# FPGA_IO_Interface.net
KiCad netlist of a schematic drawn in Altium Designer
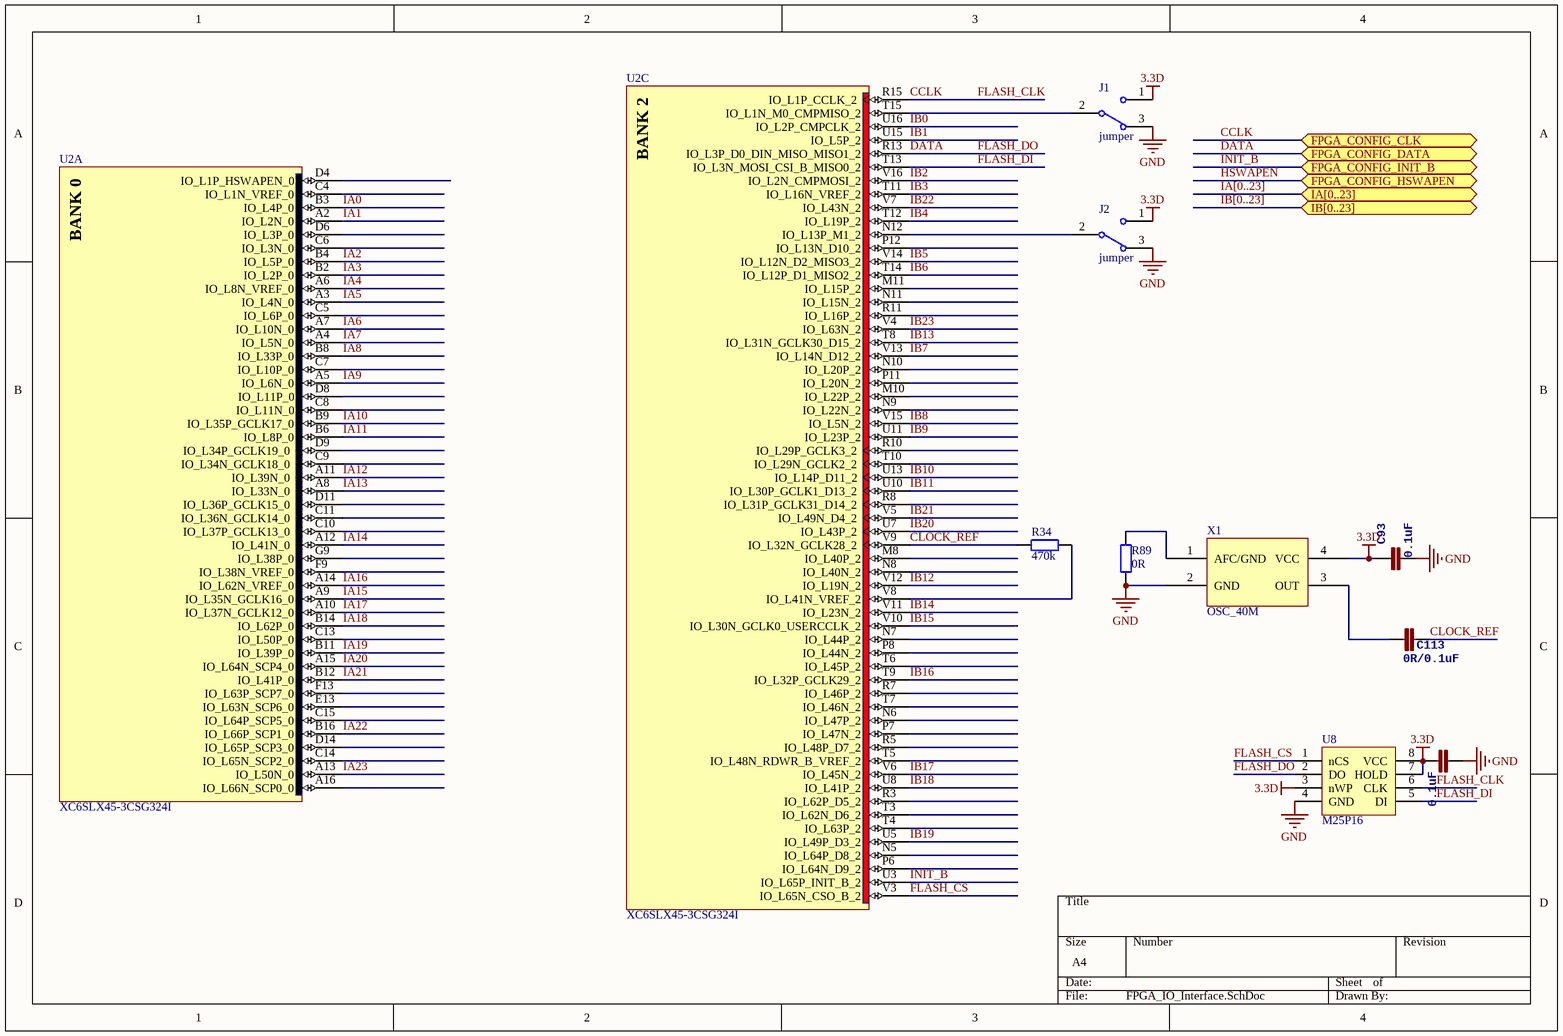
[diagram p0: FPGA_IO_Interface.SchDoc]

(export (version "E")
  (design (tool "Eeschema 10.0.6"))
  (components
    (comp (ref "C68")
      (value "0.1uF")
      (footprint "0402")
      (description "<b>Capacitor</b>\nStandard 0603 ceramic capacitor, and 0.1\" leaded capacitor.")
      (fields (field (name "PARTNO") "CC0402ZRY5V7BB104"))
      (libsource (lib "") (part "CAP0402-CAP_1"))
    )
    (comp (ref "C93")
      (value "0.1uF")
      (footprint "0402")
      (description "<b>Capacitor</b>\nStandard 0603 ceramic capacitor, and 0.1\" leaded capacitor.")
      (fields (field (name "PARTNO") "CC0402ZRY5V7BB104"))
      (libsource (lib "pixhawk2") (part "CAP0402-CAP"))
    )
    (comp (ref "C113")
      (value "0R/0.1uF")
      (footprint "0402")
      (description "<b>Capacitor</b>\nStandard 0603 ceramic capacitor, and 0.1\" leaded capacitor.")
      (fields (field (name "PARTNO") "CC0402ZRY5V7BB104"))
      (libsource (lib "pixhawk2") (part "CAP0402-CAP"))
    )
    (comp (ref "J1")
      (value "jumper")
      (footprint "0402J")
      (description "SPDT Subminiature Toggle Switch, Right Angle Mounting, Vertical Actuation")
      (fields (field (name "PUBLISHER") "Altium Limited"))
      (libsource (lib "Miscellaneous Devices") (part "SW-SPDT"))
    )
    (comp (ref "J2")
      (value "jumper")
      (footprint "0402J")
      (description "SPDT Subminiature Toggle Switch, Right Angle Mounting, Vertical Actuation")
      (fields (field (name "PUBLISHER") "Altium Limited"))
      (libsource (lib "Miscellaneous Devices") (part "SW-SPDT"))
    )
    (comp (ref "R34")
      (value "470k")
      (footprint "0402")
      (description "Resistor")
      (fields (field (name "PUBLISHER") "Altium Limited"))
      (libsource (lib "") (part "Res2_1"))
    )
    (comp (ref "R89")
      (value "0R")
      (footprint "0402")
      (description "Resistor")
      (fields (field (name "PUBLISHER") "Altium Limited"))
      (libsource (lib "Miscellaneous Devices") (part "Res2"))
    )
    (comp (ref "U2")
      (value "XC6SLX45-3CSG324I")
      (footprint "CSG324")
      (fields (field (name "PUBLISHER") "Altium Limited"))
      (libsource (lib "Xilinx Spartan-6") (part "XC6SLX45-3CSG324I"))
    )
    (comp (ref "U8") (value "M25P16") (footprint "SO8") (libsource (lib "sch") (part "M25P16")))
    (comp (ref "X1") (value "OSC_40M") (footprint "TXC_7Q") (libsource (lib "F4SDR") (part "OSC_40M")))
  )
  (nets
    (net (code "1") (name "/CCLK") (class "Default")
      (node (ref "U2") (pin "R15") (pinfunction "IO_L1P_CCLK_2_R15") (pintype "bidirectional"))
      (node (ref "U8") (pin "6") (pinfunction "CLK_6") (pintype "passive"))
    )
    (net (code "2") (name "/CLOCK_REF") (class "Default")
      (node (ref "C113") (pin "2") (pinfunction "2_2") (pintype "passive"))
      (node (ref "R34") (pin "1") (pinfunction "1_1") (pintype "passive"))
      (node (ref "U2") (pin "V9") (pinfunction "IO_L32N_GCLK28_2_V9") (pintype "bidirectional"))
    )
    (net (code "3") (name "/DATA") (class "Default")
      (node (ref "U2") (pin "R13") (pinfunction "IO_L3P_D0_DIN_MISO_MISO1_2_R13") (pintype "bidirectional"))
      (node (ref "U8") (pin "2") (pinfunction "DO_2") (pintype "passive"))
    )
    (net (code "4") (name "/FLASH_CS") (class "Default")
      (node (ref "U2") (pin "V3") (pinfunction "IO_L65N_CSO_B_2_V3") (pintype "bidirectional"))
      (node (ref "U8") (pin "1") (pinfunction "nCS_1") (pintype "passive"))
    )
    (net (code "5") (name "/FLASH_DI") (class "Default")
      (node (ref "U2") (pin "T13") (pinfunction "IO_L3N_MOSI_CSI_B_MISO0_2_T13") (pintype "bidirectional"))
      (node (ref "U8") (pin "5") (pinfunction "DI_5") (pintype "passive"))
    )
    (net (code "7") (name "/IA0") (class "Default")
      (node (ref "U2") (pin "B3") (pinfunction "IO_L4P_0_B3") (pintype "bidirectional"))
    )
    (net (code "8") (name "/IA1") (class "Default")
      (node (ref "U2") (pin "A2") (pinfunction "IO_L2N_0_A2") (pintype "bidirectional"))
    )
    (net (code "9") (name "/IA2") (class "Default")
      (node (ref "U2") (pin "B4") (pinfunction "IO_L5P_0_B4") (pintype "bidirectional"))
    )
    (net (code "10") (name "/IA3") (class "Default")
      (node (ref "U2") (pin "B2") (pinfunction "IO_L2P_0_B2") (pintype "bidirectional"))
    )
    (net (code "11") (name "/IA4") (class "Default")
      (node (ref "U2") (pin "A6") (pinfunction "IO_L8N_VREF_0_A6") (pintype "bidirectional"))
    )
    (net (code "12") (name "/IA5") (class "Default")
      (node (ref "U2") (pin "A3") (pinfunction "IO_L4N_0_A3") (pintype "bidirectional"))
    )
    (net (code "13") (name "/IA6") (class "Default")
      (node (ref "U2") (pin "A7") (pinfunction "IO_L10N_0_A7") (pintype "bidirectional"))
    )
    (net (code "14") (name "/IA7") (class "Default")
      (node (ref "U2") (pin "A4") (pinfunction "IO_L5N_0_A4") (pintype "bidirectional"))
    )
    (net (code "15") (name "/IA8") (class "Default")
      (node (ref "U2") (pin "B8") (pinfunction "IO_L33P_0_B8") (pintype "bidirectional"))
    )
    (net (code "16") (name "/IA9") (class "Default")
      (node (ref "U2") (pin "A5") (pinfunction "IO_L6N_0_A5") (pintype "bidirectional"))
    )
    (net (code "17") (name "/IA10") (class "Default")
      (node (ref "U2") (pin "B9") (pinfunction "IO_L35P_GCLK17_0_B9") (pintype "bidirectional"))
    )
    (net (code "18") (name "/IA11") (class "Default")
      (node (ref "U2") (pin "B6") (pinfunction "IO_L8P_0_B6") (pintype "bidirectional"))
    )
    (net (code "19") (name "/IA12") (class "Default")
      (node (ref "U2") (pin "A11") (pinfunction "IO_L39N_0_A11") (pintype "bidirectional"))
    )
    (net (code "20") (name "/IA13") (class "Default")
      (node (ref "U2") (pin "A8") (pinfunction "IO_L33N_0_A8") (pintype "bidirectional"))
    )
    (net (code "21") (name "/IA14") (class "Default")
      (node (ref "U2") (pin "A12") (pinfunction "IO_L41N_0_A12") (pintype "bidirectional"))
    )
    (net (code "22") (name "/IA15") (class "Default")
      (node (ref "U2") (pin "A9") (pinfunction "IO_L35N_GCLK16_0_A9") (pintype "bidirectional"))
    )
    (net (code "23") (name "/IA16") (class "Default")
      (node (ref "U2") (pin "A14") (pinfunction "IO_L62N_VREF_0_A14") (pintype "bidirectional"))
    )
    (net (code "24") (name "/IA17") (class "Default")
      (node (ref "U2") (pin "A10") (pinfunction "IO_L37N_GCLK12_0_A10") (pintype "bidirectional"))
    )
    (net (code "25") (name "/IA18") (class "Default")
      (node (ref "U2") (pin "B14") (pinfunction "IO_L62P_0_B14") (pintype "bidirectional"))
    )
    (net (code "26") (name "/IA19") (class "Default")
      (node (ref "U2") (pin "B11") (pinfunction "IO_L39P_0_B11") (pintype "bidirectional"))
    )
    (net (code "27") (name "/IA20") (class "Default")
      (node (ref "U2") (pin "A15") (pinfunction "IO_L64N_SCP4_0_A15") (pintype "bidirectional"))
    )
    (net (code "28") (name "/IA21") (class "Default")
      (node (ref "U2") (pin "B12") (pinfunction "IO_L41P_0_B12") (pintype "bidirectional"))
    )
    (net (code "29") (name "/IA22") (class "Default")
      (node (ref "U2") (pin "B16") (pinfunction "IO_L66P_SCP1_0_B16") (pintype "bidirectional"))
    )
    (net (code "30") (name "/IA23") (class "Default")
      (node (ref "U2") (pin "A13") (pinfunction "IO_L50N_0_A13") (pintype "bidirectional"))
    )
    (net (code "32") (name "/IB0") (class "Default")
      (node (ref "U2") (pin "U16") (pinfunction "IO_L2P_CMPCLK_2_U16") (pintype "bidirectional"))
    )
    (net (code "33") (name "/IB1") (class "Default")
      (node (ref "U2") (pin "U15") (pinfunction "IO_L5P_2_U15") (pintype "bidirectional"))
    )
    (net (code "34") (name "/IB2") (class "Default")
      (node (ref "U2") (pin "V16") (pinfunction "IO_L2N_CMPMOSI_2_V16") (pintype "bidirectional"))
    )
    (net (code "35") (name "/IB3") (class "Default")
      (node (ref "U2") (pin "T11") (pinfunction "IO_L16N_VREF_2_T11") (pintype "bidirectional"))
    )
    (net (code "36") (name "/IB4") (class "Default")
      (node (ref "U2") (pin "T12") (pinfunction "IO_L19P_2_T12") (pintype "bidirectional"))
    )
    (net (code "37") (name "/IB5") (class "Default")
      (node (ref "U2") (pin "V14") (pinfunction "IO_L12N_D2_MISO3_2_V14") (pintype "bidirectional"))
    )
    (net (code "38") (name "/IB6") (class "Default")
      (node (ref "U2") (pin "T14") (pinfunction "IO_L12P_D1_MISO2_2_T14") (pintype "bidirectional"))
    )
    (net (code "39") (name "/IB7") (class "Default")
      (node (ref "U2") (pin "V13") (pinfunction "IO_L14N_D12_2_V13") (pintype "bidirectional"))
    )
    (net (code "40") (name "/IB8") (class "Default")
      (node (ref "U2") (pin "V15") (pinfunction "IO_L5N_2_V15") (pintype "bidirectional"))
    )
    (net (code "41") (name "/IB9") (class "Default")
      (node (ref "U2") (pin "U11") (pinfunction "IO_L23P_2_U11") (pintype "bidirectional"))
    )
    (net (code "42") (name "/IB10") (class "Default")
      (node (ref "U2") (pin "U13") (pinfunction "IO_L14P_D11_2_U13") (pintype "bidirectional"))
    )
    (net (code "43") (name "/IB11") (class "Default")
      (node (ref "U2") (pin "U10") (pinfunction "IO_L30P_GCLK1_D13_2_U10") (pintype "bidirectional"))
    )
    (net (code "44") (name "/IB12") (class "Default")
      (node (ref "U2") (pin "V12") (pinfunction "IO_L19N_2_V12") (pintype "bidirectional"))
    )
    (net (code "45") (name "/IB13") (class "Default")
      (node (ref "U2") (pin "T8") (pinfunction "IO_L31N_GCLK30_D15_2_T8") (pintype "bidirectional"))
    )
    (net (code "46") (name "/IB14") (class "Default")
      (node (ref "U2") (pin "V11") (pinfunction "IO_L23N_2_V11") (pintype "bidirectional"))
    )
    (net (code "47") (name "/IB15") (class "Default")
      (node (ref "U2") (pin "V10") (pinfunction "IO_L30N_GCLK0_USERCCLK_2_V10") (pintype "bidirectional"))
    )
    (net (code "48") (name "/IB16") (class "Default")
      (node (ref "U2") (pin "T9") (pinfunction "IO_L32P_GCLK29_2_T9") (pintype "bidirectional"))
    )
    (net (code "49") (name "/IB17") (class "Default")
      (node (ref "U2") (pin "V6") (pinfunction "IO_L45N_2_V6") (pintype "bidirectional"))
    )
    (net (code "50") (name "/IB18") (class "Default")
      (node (ref "U2") (pin "U8") (pinfunction "IO_L41P_2_U8") (pintype "bidirectional"))
    )
    (net (code "51") (name "/IB19") (class "Default")
      (node (ref "U2") (pin "U5") (pinfunction "IO_L49P_D3_2_U5") (pintype "bidirectional"))
    )
    (net (code "52") (name "/IB20") (class "Default")
      (node (ref "U2") (pin "U7") (pinfunction "IO_L43P_2_U7") (pintype "bidirectional"))
    )
    (net (code "53") (name "/IB21") (class "Default")
      (node (ref "U2") (pin "V5") (pinfunction "IO_L49N_D4_2_V5") (pintype "bidirectional"))
    )
    (net (code "54") (name "/IB22") (class "Default")
      (node (ref "U2") (pin "V7") (pinfunction "IO_L43N_2_V7") (pintype "bidirectional"))
    )
    (net (code "55") (name "/IB23") (class "Default")
      (node (ref "U2") (pin "V4") (pinfunction "IO_L63N_2_V4") (pintype "bidirectional"))
    )
    (net (code "57") (name "/INIT_B") (class "Default")
      (node (ref "U2") (pin "U3") (pinfunction "IO_L65P_INIT_B_2_U3") (pintype "bidirectional"))
    )
    (net (code "58") (name "3.3D") (class "Default")
      (node (ref "C68") (pin "2") (pinfunction "2_2") (pintype "passive"))
      (node (ref "C93") (pin "1") (pinfunction "1_1") (pintype "passive"))
      (node (ref "J1") (pin "1") (pinfunction "1_1") (pintype "passive"))
      (node (ref "J2") (pin "1") (pinfunction "1_1") (pintype "passive"))
      (node (ref "U8") (pin "3") (pinfunction "nWP_3") (pintype "passive"))
      (node (ref "U8") (pin "7") (pinfunction "HOLD_7") (pintype "passive"))
      (node (ref "U8") (pin "8") (pinfunction "VCC_8") (pintype "passive"))
      (node (ref "X1") (pin "4") (pinfunction "VCC_4") (pintype "passive"))
    )
    (net (code "59") (name "GND") (class "Default")
      (node (ref "C68") (pin "1") (pinfunction "1_1") (pintype "passive"))
      (node (ref "C93") (pin "2") (pinfunction "2_2") (pintype "passive"))
      (node (ref "J1") (pin "3") (pinfunction "3_3") (pintype "passive"))
      (node (ref "J2") (pin "3") (pinfunction "3_3") (pintype "passive"))
      (node (ref "R89") (pin "2") (pinfunction "2_2") (pintype "passive"))
      (node (ref "U8") (pin "4") (pinfunction "GND_4") (pintype "passive"))
      (node (ref "X1") (pin "2") (pinfunction "GND_2") (pintype "passive"))
    )
    (net (code "60") (name "Net-(U2C-IO_L1N_M0_CMPMISO_2)") (class "Default")
      (node (ref "J1") (pin "2") (pinfunction "2_2") (pintype "passive"))
      (node (ref "U2") (pin "T15") (pinfunction "IO_L1N_M0_CMPMISO_2_T15") (pintype "bidirectional"))
    )
    (net (code "61") (name "Net-(U2C-IO_L13P_M1_2)") (class "Default")
      (node (ref "J2") (pin "2") (pinfunction "2_2") (pintype "passive"))
      (node (ref "U2") (pin "N12") (pinfunction "IO_L13P_M1_2_N12") (pintype "bidirectional"))
    )
    (net (code "62") (name "Net-(U2C-IO_L41N_VREF_2)") (class "Default")
      (node (ref "R34") (pin "2") (pinfunction "2_2") (pintype "passive"))
      (node (ref "U2") (pin "V8") (pinfunction "IO_L41N_VREF_2_V8") (pintype "bidirectional"))
    )
    (net (code "63") (name "Net-(X1-AFC{slash}GND)") (class "Default")
      (node (ref "R89") (pin "1") (pinfunction "1_1") (pintype "passive"))
      (node (ref "X1") (pin "1") (pinfunction "AFC/GND_1") (pintype "passive"))
    )
    (net (code "64") (name "Net-(X1-OUT)") (class "Default")
      (node (ref "C113") (pin "1") (pinfunction "1_1") (pintype "passive"))
      (node (ref "X1") (pin "3") (pinfunction "OUT_3") (pintype "passive"))
    )
    (net (code "65") (name "unconnected-(U2A-IO_L1N_VREF_0-PadC4)") (class "Default")
      (node (ref "U2") (pin "C4") (pinfunction "IO_L1N_VREF_0_C4") (pintype "bidirectional"))
    )
    (net (code "66") (name "unconnected-(U2A-IO_L1P_HSWAPEN_0-PadD4)") (class "Default")
      (node (ref "U2") (pin "D4") (pinfunction "IO_L1P_HSWAPEN_0_D4") (pintype "bidirectional"))
    )
    (net (code "67") (name "unconnected-(U2A-IO_L3N_0-PadC6)") (class "Default")
      (node (ref "U2") (pin "C6") (pinfunction "IO_L3N_0_C6") (pintype "bidirectional"))
    )
    (net (code "68") (name "unconnected-(U2A-IO_L3P_0-PadD6)") (class "Default")
      (node (ref "U2") (pin "D6") (pinfunction "IO_L3P_0_D6") (pintype "bidirectional"))
    )
    (net (code "69") (name "unconnected-(U2A-IO_L6P_0-PadC5)") (class "Default")
      (node (ref "U2") (pin "C5") (pinfunction "IO_L6P_0_C5") (pintype "bidirectional"))
    )
    (net (code "70") (name "unconnected-(U2A-IO_L10P_0-PadC7)") (class "Default")
      (node (ref "U2") (pin "C7") (pinfunction "IO_L10P_0_C7") (pintype "bidirectional"))
    )
    (net (code "71") (name "unconnected-(U2A-IO_L11N_0-PadC8)") (class "Default")
      (node (ref "U2") (pin "C8") (pinfunction "IO_L11N_0_C8") (pintype "bidirectional"))
    )
    (net (code "72") (name "unconnected-(U2A-IO_L11P_0-PadD8)") (class "Default")
      (node (ref "U2") (pin "D8") (pinfunction "IO_L11P_0_D8") (pintype "bidirectional"))
    )
    (net (code "73") (name "unconnected-(U2A-IO_L34N_GCLK18_0-PadC9)") (class "Default")
      (node (ref "U2") (pin "C9") (pinfunction "IO_L34N_GCLK18_0_C9") (pintype "bidirectional"))
    )
    (net (code "74") (name "unconnected-(U2A-IO_L34P_GCLK19_0-PadD9)") (class "Default")
      (node (ref "U2") (pin "D9") (pinfunction "IO_L34P_GCLK19_0_D9") (pintype "bidirectional"))
    )
    (net (code "75") (name "unconnected-(U2A-IO_L36N_GCLK14_0-PadC11)") (class "Default")
      (node (ref "U2") (pin "C11") (pinfunction "IO_L36N_GCLK14_0_C11") (pintype "bidirectional"))
    )
    (net (code "76") (name "unconnected-(U2A-IO_L36P_GCLK15_0-PadD11)") (class "Default")
      (node (ref "U2") (pin "D11") (pinfunction "IO_L36P_GCLK15_0_D11") (pintype "bidirectional"))
    )
    (net (code "77") (name "unconnected-(U2A-IO_L37P_GCLK13_0-PadC10)") (class "Default")
      (node (ref "U2") (pin "C10") (pinfunction "IO_L37P_GCLK13_0_C10") (pintype "bidirectional"))
    )
    (net (code "78") (name "unconnected-(U2A-IO_L38N_VREF_0-PadF9)") (class "Default")
      (node (ref "U2") (pin "F9") (pinfunction "IO_L38N_VREF_0_F9") (pintype "bidirectional"))
    )
    (net (code "79") (name "unconnected-(U2A-IO_L38P_0-PadG9)") (class "Default")
      (node (ref "U2") (pin "G9") (pinfunction "IO_L38P_0_G9") (pintype "bidirectional"))
    )
    (net (code "80") (name "unconnected-(U2A-IO_L50P_0-PadC13)") (class "Default")
      (node (ref "U2") (pin "C13") (pinfunction "IO_L50P_0_C13") (pintype "bidirectional"))
    )
    (net (code "81") (name "unconnected-(U2A-IO_L63N_SCP6_0-PadE13)") (class "Default")
      (node (ref "U2") (pin "E13") (pinfunction "IO_L63N_SCP6_0_E13") (pintype "bidirectional"))
    )
    (net (code "82") (name "unconnected-(U2A-IO_L63P_SCP7_0-PadF13)") (class "Default")
      (node (ref "U2") (pin "F13") (pinfunction "IO_L63P_SCP7_0_F13") (pintype "bidirectional"))
    )
    (net (code "83") (name "unconnected-(U2A-IO_L64P_SCP5_0-PadC15)") (class "Default")
      (node (ref "U2") (pin "C15") (pinfunction "IO_L64P_SCP5_0_C15") (pintype "bidirectional"))
    )
    (net (code "84") (name "unconnected-(U2A-IO_L65N_SCP2_0-PadC14)") (class "Default")
      (node (ref "U2") (pin "C14") (pinfunction "IO_L65N_SCP2_0_C14") (pintype "bidirectional"))
    )
    (net (code "85") (name "unconnected-(U2A-IO_L65P_SCP3_0-PadD14)") (class "Default")
      (node (ref "U2") (pin "D14") (pinfunction "IO_L65P_SCP3_0_D14") (pintype "bidirectional"))
    )
    (net (code "86") (name "unconnected-(U2A-IO_L66N_SCP0_0-PadA16)") (class "Default")
      (node (ref "U2") (pin "A16") (pinfunction "IO_L66N_SCP0_0_A16") (pintype "bidirectional"))
    )
    (net (code "87") (name "unconnected-(U2C-IO_L13N_D10_2-PadP12)") (class "Default")
      (node (ref "U2") (pin "P12") (pinfunction "IO_L13N_D10_2_P12") (pintype "bidirectional"))
    )
    (net (code "88") (name "unconnected-(U2C-IO_L15N_2-PadN11)") (class "Default")
      (node (ref "U2") (pin "N11") (pinfunction "IO_L15N_2_N11") (pintype "bidirectional"))
    )
    (net (code "89") (name "unconnected-(U2C-IO_L15P_2-PadM11)") (class "Default")
      (node (ref "U2") (pin "M11") (pinfunction "IO_L15P_2_M11") (pintype "bidirectional"))
    )
    (net (code "90") (name "unconnected-(U2C-IO_L16P_2-PadR11)") (class "Default")
      (node (ref "U2") (pin "R11") (pinfunction "IO_L16P_2_R11") (pintype "bidirectional"))
    )
    (net (code "91") (name "unconnected-(U2C-IO_L20N_2-PadP11)") (class "Default")
      (node (ref "U2") (pin "P11") (pinfunction "IO_L20N_2_P11") (pintype "bidirectional"))
    )
    (net (code "92") (name "unconnected-(U2C-IO_L20P_2-PadN10)") (class "Default")
      (node (ref "U2") (pin "N10") (pinfunction "IO_L20P_2_N10") (pintype "bidirectional"))
    )
    (net (code "93") (name "unconnected-(U2C-IO_L22N_2-PadN9)") (class "Default")
      (node (ref "U2") (pin "N9") (pinfunction "IO_L22N_2_N9") (pintype "bidirectional"))
    )
    (net (code "94") (name "unconnected-(U2C-IO_L22P_2-PadM10)") (class "Default")
      (node (ref "U2") (pin "M10") (pinfunction "IO_L22P_2_M10") (pintype "bidirectional"))
    )
    (net (code "95") (name "unconnected-(U2C-IO_L29N_GCLK2_2-PadT10)") (class "Default")
      (node (ref "U2") (pin "T10") (pinfunction "IO_L29N_GCLK2_2_T10") (pintype "bidirectional"))
    )
    (net (code "96") (name "unconnected-(U2C-IO_L29P_GCLK3_2-PadR10)") (class "Default")
      (node (ref "U2") (pin "R10") (pinfunction "IO_L29P_GCLK3_2_R10") (pintype "bidirectional"))
    )
    (net (code "97") (name "unconnected-(U2C-IO_L31P_GCLK31_D14_2-PadR8)") (class "Default")
      (node (ref "U2") (pin "R8") (pinfunction "IO_L31P_GCLK31_D14_2_R8") (pintype "bidirectional"))
    )
    (net (code "98") (name "unconnected-(U2C-IO_L40N_2-PadN8)") (class "Default")
      (node (ref "U2") (pin "N8") (pinfunction "IO_L40N_2_N8") (pintype "bidirectional"))
    )
    (net (code "99") (name "unconnected-(U2C-IO_L40P_2-PadM8)") (class "Default")
      (node (ref "U2") (pin "M8") (pinfunction "IO_L40P_2_M8") (pintype "bidirectional"))
    )
    (net (code "100") (name "unconnected-(U2C-IO_L44N_2-PadP8)") (class "Default")
      (node (ref "U2") (pin "P8") (pinfunction "IO_L44N_2_P8") (pintype "bidirectional"))
    )
    (net (code "101") (name "unconnected-(U2C-IO_L44P_2-PadN7)") (class "Default")
      (node (ref "U2") (pin "N7") (pinfunction "IO_L44P_2_N7") (pintype "bidirectional"))
    )
    (net (code "102") (name "unconnected-(U2C-IO_L45P_2-PadT6)") (class "Default")
      (node (ref "U2") (pin "T6") (pinfunction "IO_L45P_2_T6") (pintype "bidirectional"))
    )
    (net (code "103") (name "unconnected-(U2C-IO_L46N_2-PadT7)") (class "Default")
      (node (ref "U2") (pin "T7") (pinfunction "IO_L46N_2_T7") (pintype "bidirectional"))
    )
    (net (code "104") (name "unconnected-(U2C-IO_L46P_2-PadR7)") (class "Default")
      (node (ref "U2") (pin "R7") (pinfunction "IO_L46P_2_R7") (pintype "bidirectional"))
    )
    (net (code "105") (name "unconnected-(U2C-IO_L47N_2-PadP7)") (class "Default")
      (node (ref "U2") (pin "P7") (pinfunction "IO_L47N_2_P7") (pintype "bidirectional"))
    )
    (net (code "106") (name "unconnected-(U2C-IO_L47P_2-PadN6)") (class "Default")
      (node (ref "U2") (pin "N6") (pinfunction "IO_L47P_2_N6") (pintype "bidirectional"))
    )
    (net (code "107") (name "unconnected-(U2C-IO_L48N_RDWR_B_VREF_2-PadT5)") (class "Default")
      (node (ref "U2") (pin "T5") (pinfunction "IO_L48N_RDWR_B_VREF_2_T5") (pintype "bidirectional"))
    )
    (net (code "108") (name "unconnected-(U2C-IO_L48P_D7_2-PadR5)") (class "Default")
      (node (ref "U2") (pin "R5") (pinfunction "IO_L48P_D7_2_R5") (pintype "bidirectional"))
    )
    (net (code "109") (name "unconnected-(U2C-IO_L62N_D6_2-PadT3)") (class "Default")
      (node (ref "U2") (pin "T3") (pinfunction "IO_L62N_D6_2_T3") (pintype "bidirectional"))
    )
    (net (code "110") (name "unconnected-(U2C-IO_L62P_D5_2-PadR3)") (class "Default")
      (node (ref "U2") (pin "R3") (pinfunction "IO_L62P_D5_2_R3") (pintype "bidirectional"))
    )
    (net (code "111") (name "unconnected-(U2C-IO_L63P_2-PadT4)") (class "Default")
      (node (ref "U2") (pin "T4") (pinfunction "IO_L63P_2_T4") (pintype "bidirectional"))
    )
    (net (code "112") (name "unconnected-(U2C-IO_L64N_D9_2-PadP6)") (class "Default")
      (node (ref "U2") (pin "P6") (pinfunction "IO_L64N_D9_2_P6") (pintype "bidirectional"))
    )
    (net (code "113") (name "unconnected-(U2C-IO_L64P_D8_2-PadN5)") (class "Default")
      (node (ref "U2") (pin "N5") (pinfunction "IO_L64P_D8_2_N5") (pintype "bidirectional"))
    )
  )
)
